# bmc.net
KiCad netlist of a schematic drawn in EAGLE
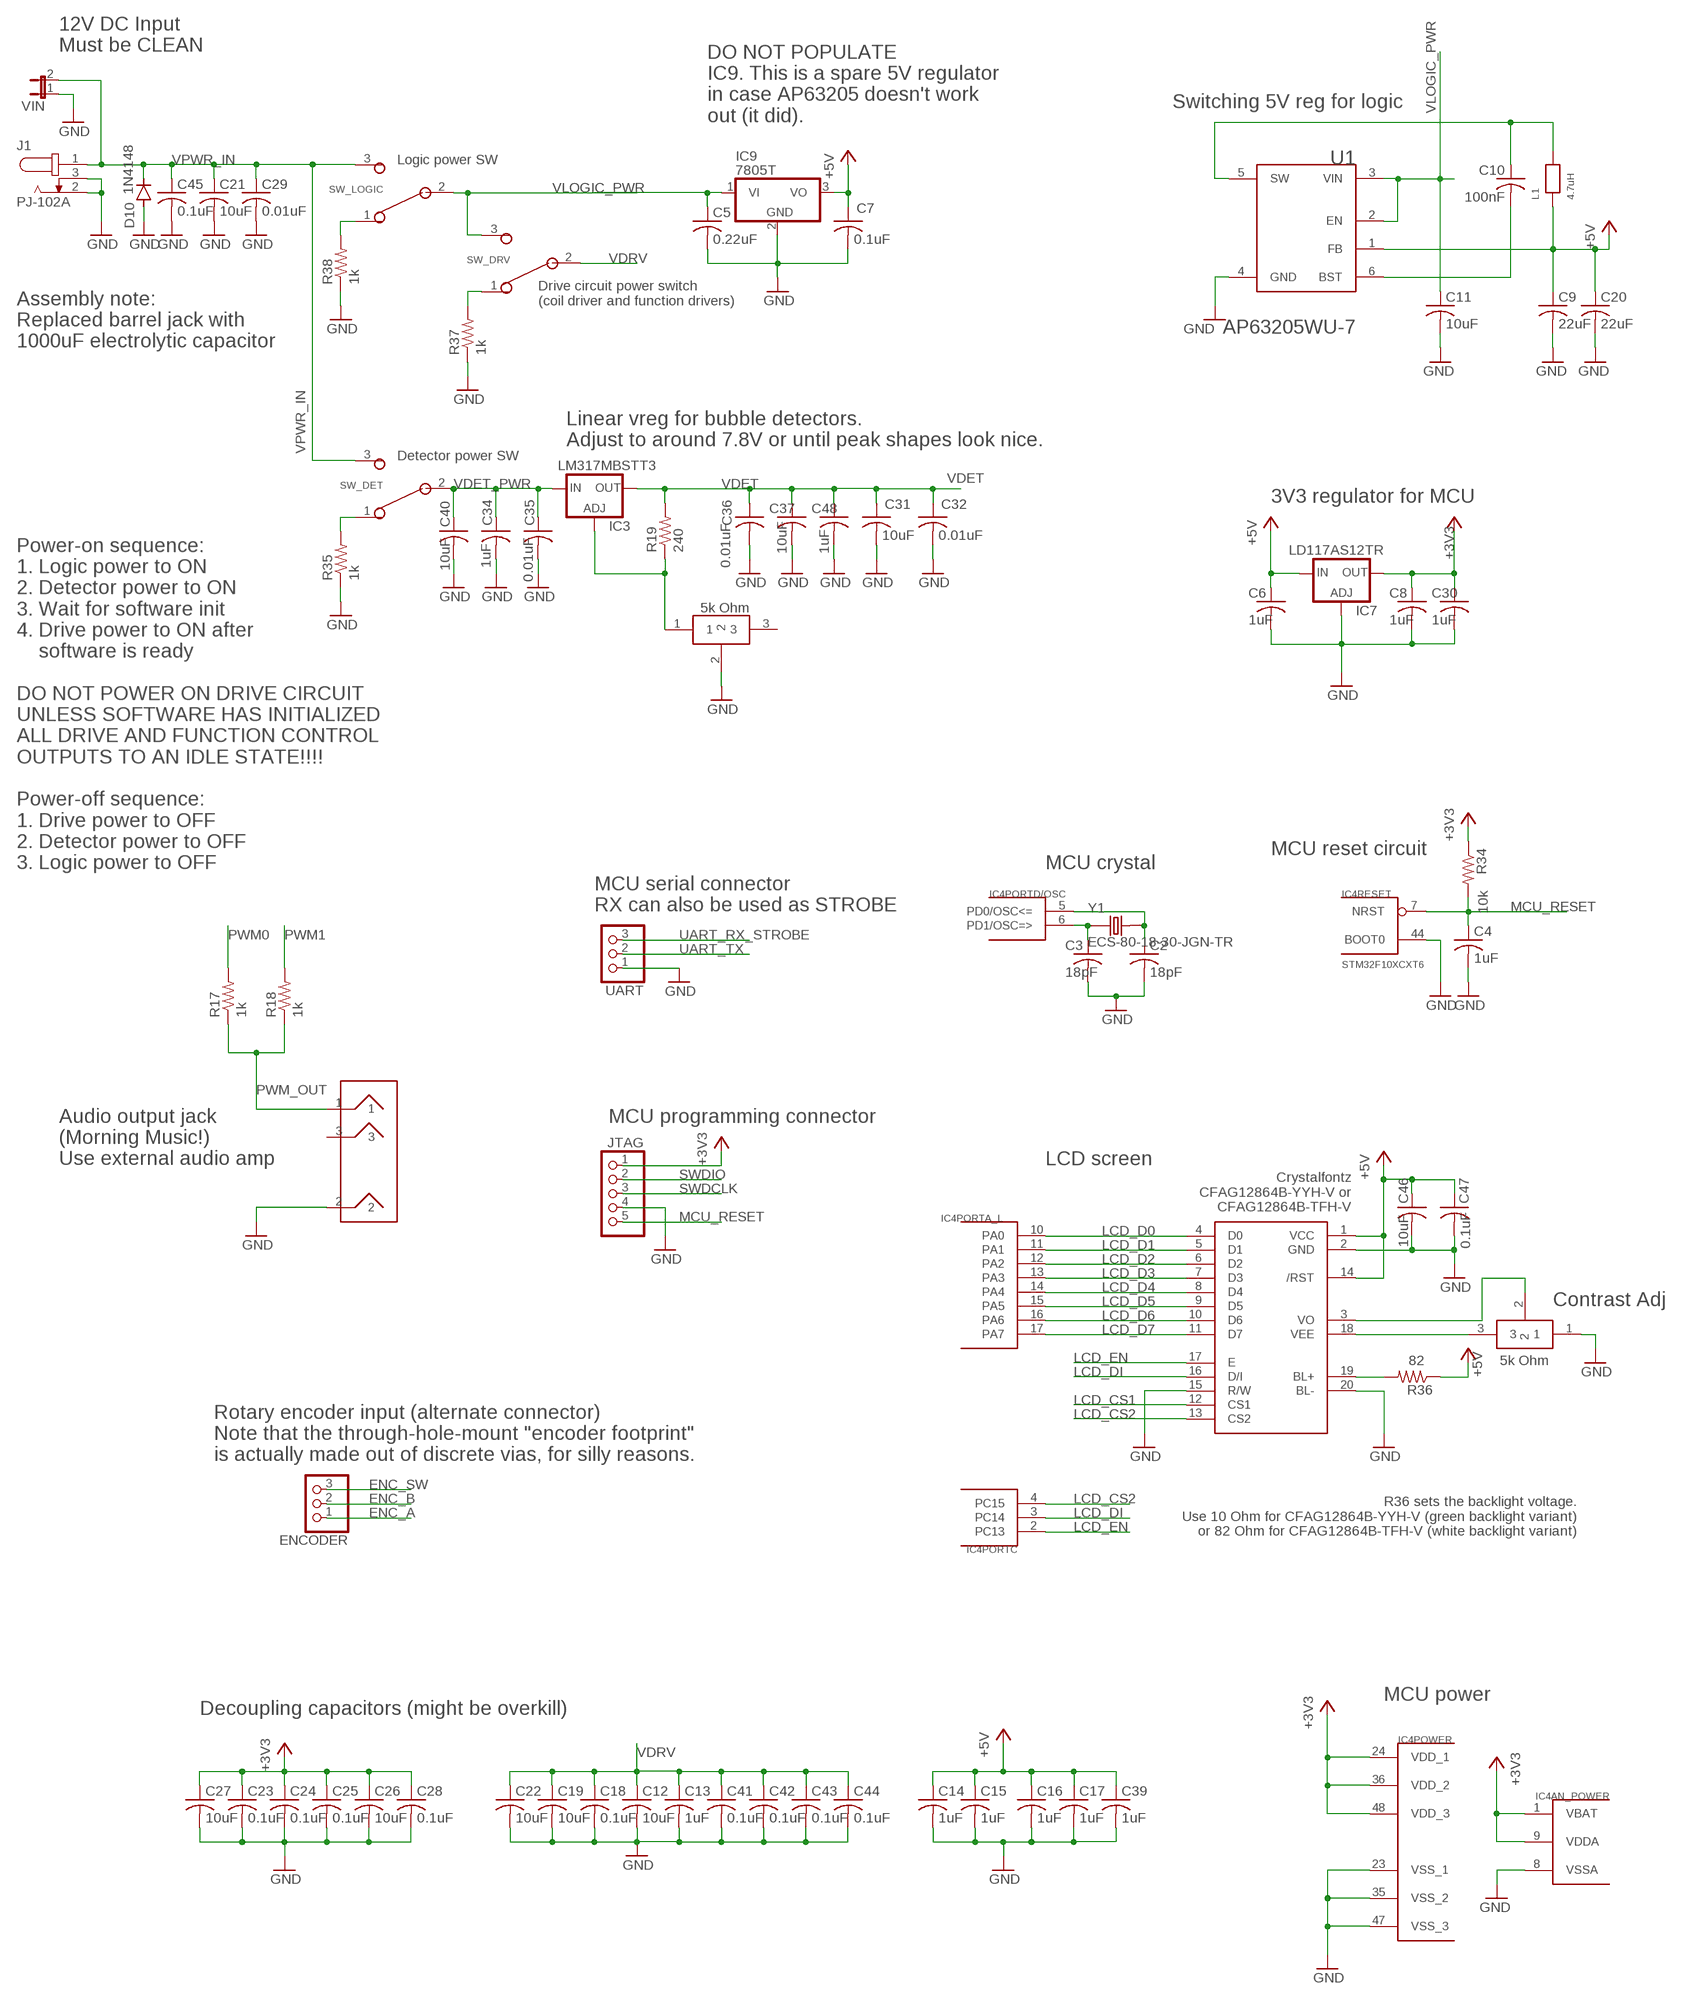
[diagram p0: schematic, sheet 1, part 1 of 2]
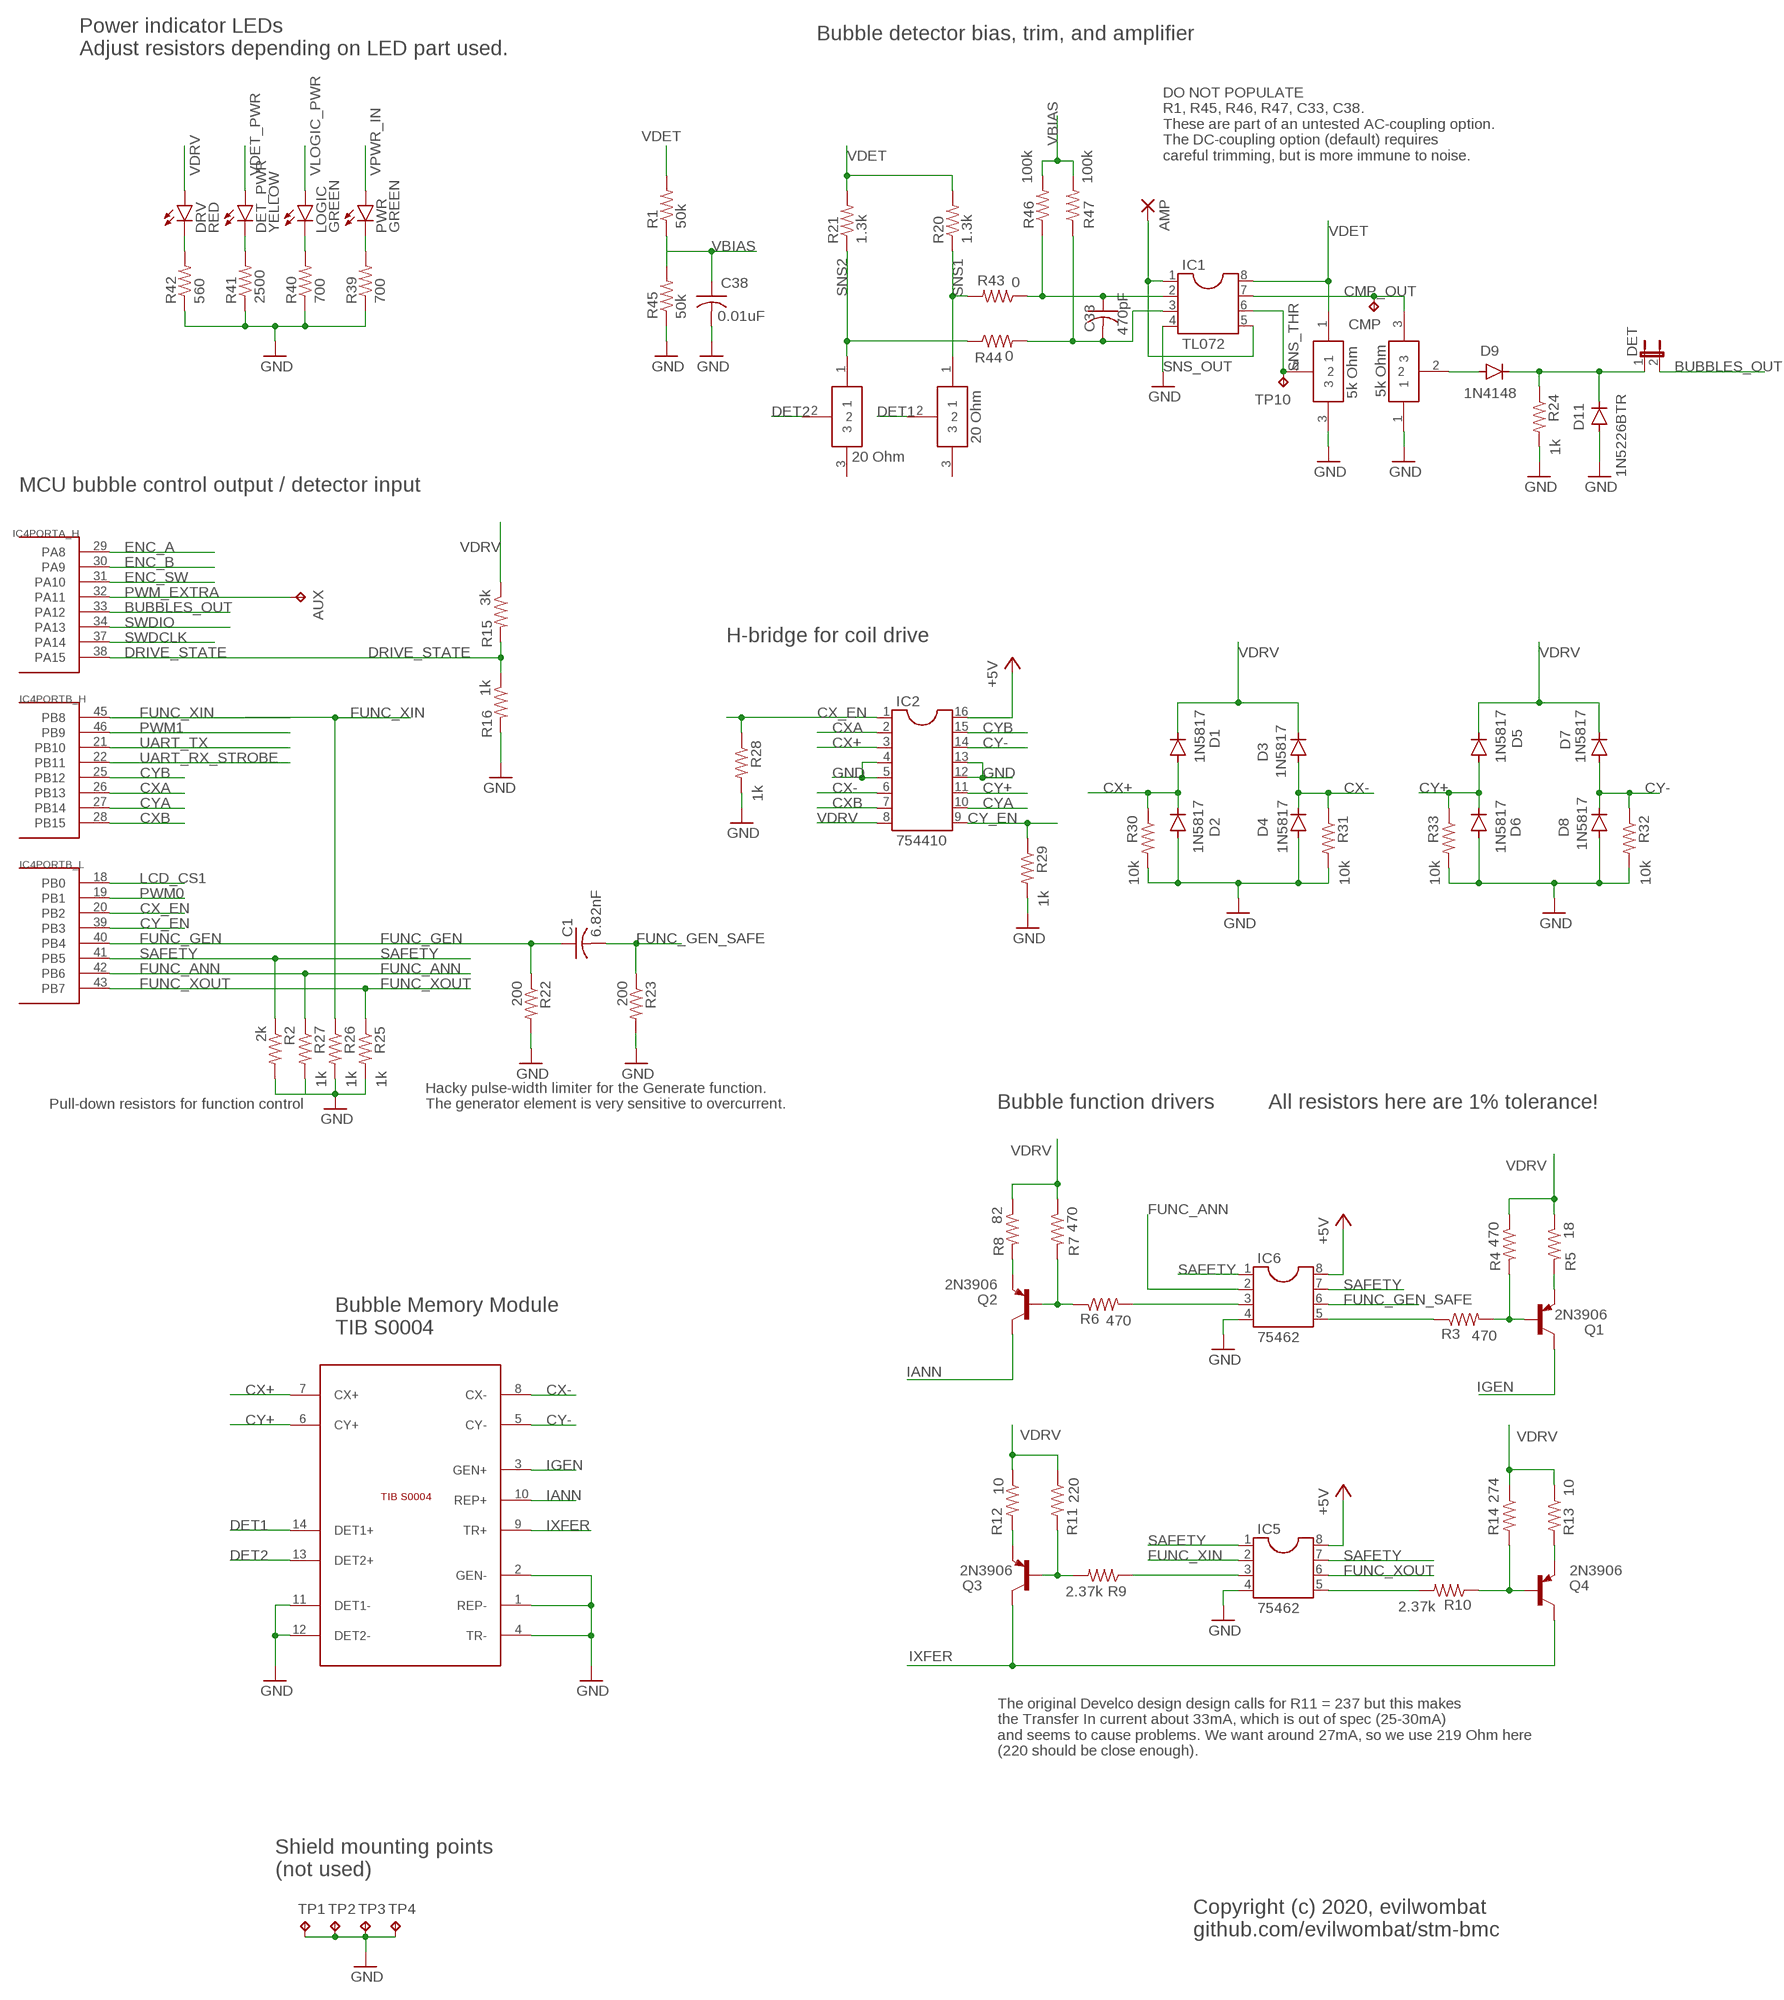
[diagram p1: schematic, sheet 1, part 2 of 2]

(export (version "E")
  (design (tool "Eeschema 10.0.6"))
  (components
    (comp (ref "AMP")
      (value "1,6/0,8")
      (footprint "eagle-import:1,6_0,8")
      (libsource (lib "eagle-import") (part "1,6/0,8"))
    )
    (comp (ref "AUX")
      (value "TPTP07R")
      (footprint "eagle-import:TP07R")
      (libsource (lib "eagle-import") (part "TPTP07R"))
    )
    (comp (ref "C1")
      (value "6.82nF")
      (footprint "eagle-import:CAPC2012X110")
      (libsource (lib "eagle-import") (part "C-USCHIP-0805(2012-METRIC)_"))
    )
    (comp (ref "C2")
      (value "18pF")
      (footprint "eagle-import:CAPC2012X110")
      (libsource (lib "eagle-import") (part "C-USCHIP-0805(2012-METRIC)_"))
    )
    (comp (ref "C3")
      (value "18pF")
      (footprint "eagle-import:CAPC2012X110")
      (libsource (lib "eagle-import") (part "C-USCHIP-0805(2012-METRIC)_"))
    )
    (comp (ref "C4")
      (value "1uF")
      (footprint "eagle-import:CAPC2012X110")
      (libsource (lib "eagle-import") (part "C-USCHIP-0805(2012-METRIC)_"))
    )
    (comp (ref "C5")
      (value "0.22uF")
      (footprint "eagle-import:CAPC2012X110")
      (libsource (lib "eagle-import") (part "C-USCHIP-0805(2012-METRIC)_"))
    )
    (comp (ref "C6")
      (value "1uF")
      (footprint "eagle-import:CAPC2012X110")
      (libsource (lib "eagle-import") (part "C-USCHIP-0805(2012-METRIC)_"))
    )
    (comp (ref "C7")
      (value "0.1uF")
      (footprint "eagle-import:CAPC2012X110")
      (libsource (lib "eagle-import") (part "C-USCHIP-0805(2012-METRIC)_"))
    )
    (comp (ref "C8")
      (value "1uF")
      (footprint "eagle-import:CAPC2012X110")
      (libsource (lib "eagle-import") (part "C-USCHIP-0805(2012-METRIC)_"))
    )
    (comp (ref "C9")
      (value "22uF")
      (footprint "eagle-import:CAPC2012X110")
      (libsource (lib "eagle-import") (part "C-USCHIP-0805(2012-METRIC)_"))
    )
    (comp (ref "C10")
      (value "100nF")
      (footprint "eagle-import:CAPC2012X110")
      (libsource (lib "eagle-import") (part "C-USCHIP-0805(2012-METRIC)_"))
    )
    (comp (ref "C11")
      (value "10uF")
      (footprint "eagle-import:CAPC3216X135")
      (libsource (lib "eagle-import") (part "C-USCHIP-1206(3216-METRIC)_"))
    )
    (comp (ref "C12")
      (value "10uF")
      (footprint "eagle-import:CAPC3216X135")
      (libsource (lib "eagle-import") (part "C-USCHIP-1206(3216-METRIC)_"))
    )
    (comp (ref "C13")
      (value "1uF")
      (footprint "eagle-import:CAPC2012X110")
      (libsource (lib "eagle-import") (part "C-USCHIP-0805(2012-METRIC)_"))
    )
    (comp (ref "C14")
      (value "1uF")
      (footprint "eagle-import:CAPC2012X110")
      (libsource (lib "eagle-import") (part "C-USCHIP-0805(2012-METRIC)_"))
    )
    (comp (ref "C15")
      (value "1uF")
      (footprint "eagle-import:CAPC2012X110")
      (libsource (lib "eagle-import") (part "C-USCHIP-0805(2012-METRIC)_"))
    )
    (comp (ref "C16")
      (value "1uF")
      (footprint "eagle-import:CAPC2012X110")
      (libsource (lib "eagle-import") (part "C-USCHIP-0805(2012-METRIC)_"))
    )
    (comp (ref "C17")
      (value "1uF")
      (footprint "eagle-import:CAPC2012X110")
      (libsource (lib "eagle-import") (part "C-USCHIP-0805(2012-METRIC)_"))
    )
    (comp (ref "C18")
      (value "0.1uF")
      (footprint "eagle-import:CAPC2012X110")
      (libsource (lib "eagle-import") (part "C-USCHIP-0805(2012-METRIC)_"))
    )
    (comp (ref "C19")
      (value "10uF")
      (footprint "eagle-import:CAPC3216X135")
      (libsource (lib "eagle-import") (part "C-USCHIP-1206(3216-METRIC)_"))
    )
    (comp (ref "C20")
      (value "22uF")
      (footprint "eagle-import:CAPC2012X110")
      (libsource (lib "eagle-import") (part "C-USCHIP-0805(2012-METRIC)_"))
    )
    (comp (ref "C21")
      (value "10uF")
      (footprint "eagle-import:CAPC3216X135")
      (libsource (lib "eagle-import") (part "C-USCHIP-1206(3216-METRIC)_"))
    )
    (comp (ref "C22")
      (value "10uF")
      (footprint "eagle-import:CAPC3216X135")
      (libsource (lib "eagle-import") (part "C-USCHIP-1206(3216-METRIC)_"))
    )
    (comp (ref "C23")
      (value "0.1uF")
      (footprint "eagle-import:CAPC1005X60")
      (libsource (lib "eagle-import") (part "C-USCHIP-0402(1005-METRIC)_"))
    )
    (comp (ref "C24")
      (value "0.1uF")
      (footprint "eagle-import:CAPC1005X60")
      (libsource (lib "eagle-import") (part "C-USCHIP-0402(1005-METRIC)_"))
    )
    (comp (ref "C25")
      (value "0.1uF")
      (footprint "eagle-import:CAPC1005X60")
      (libsource (lib "eagle-import") (part "C-USCHIP-0402(1005-METRIC)_"))
    )
    (comp (ref "C26")
      (value "10uF")
      (footprint "eagle-import:CAPC2012X110")
      (libsource (lib "eagle-import") (part "C-USCHIP-0805(2012-METRIC)_"))
    )
    (comp (ref "C27")
      (value "10uF")
      (footprint "eagle-import:CAPC2012X110")
      (libsource (lib "eagle-import") (part "C-USCHIP-0805(2012-METRIC)_"))
    )
    (comp (ref "C28")
      (value "0.1uF")
      (footprint "eagle-import:CAPC1005X60")
      (libsource (lib "eagle-import") (part "C-USCHIP-0402(1005-METRIC)_"))
    )
    (comp (ref "C29")
      (value "0.01uF")
      (footprint "eagle-import:CAPC2012X110")
      (libsource (lib "eagle-import") (part "C-USCHIP-0805(2012-METRIC)_"))
    )
    (comp (ref "C30")
      (value "1uF")
      (footprint "eagle-import:CAPC2012X110")
      (libsource (lib "eagle-import") (part "C-USCHIP-0805(2012-METRIC)_"))
    )
    (comp (ref "C31")
      (value "10uF")
      (footprint "eagle-import:CAPC3216X135")
      (libsource (lib "eagle-import") (part "C-USCHIP-1206(3216-METRIC)_"))
    )
    (comp (ref "C32")
      (value "0.01uF")
      (footprint "eagle-import:CAPC2012X110")
      (libsource (lib "eagle-import") (part "C-USCHIP-0805(2012-METRIC)_"))
    )
    (comp (ref "C33")
      (value "470pF")
      (footprint "eagle-import:CAPC2012X110")
      (libsource (lib "eagle-import") (part "C-USCHIP-0805(2012-METRIC)_"))
    )
    (comp (ref "C34")
      (value "1uF")
      (footprint "eagle-import:CAPC2012X110")
      (libsource (lib "eagle-import") (part "C-USCHIP-0805(2012-METRIC)_"))
    )
    (comp (ref "C35")
      (value "0.01uF")
      (footprint "eagle-import:CAPC2012X110")
      (libsource (lib "eagle-import") (part "C-USCHIP-0805(2012-METRIC)_"))
    )
    (comp (ref "C36")
      (value "0.01uF")
      (footprint "eagle-import:CAPC2012X110")
      (libsource (lib "eagle-import") (part "C-USCHIP-0805(2012-METRIC)_"))
    )
    (comp (ref "C37")
      (value "10uF")
      (footprint "eagle-import:CAPC3216X135")
      (libsource (lib "eagle-import") (part "C-USCHIP-1206(3216-METRIC)_"))
    )
    (comp (ref "C38")
      (value "0.01uF")
      (footprint "eagle-import:CAPC2012X110")
      (libsource (lib "eagle-import") (part "C-USCHIP-0805(2012-METRIC)_"))
    )
    (comp (ref "C39")
      (value "1uF")
      (footprint "eagle-import:CAPC2012X110")
      (libsource (lib "eagle-import") (part "C-USCHIP-0805(2012-METRIC)_"))
    )
    (comp (ref "C40")
      (value "10uF")
      (footprint "eagle-import:CAPC3216X135")
      (libsource (lib "eagle-import") (part "C-USCHIP-1206(3216-METRIC)_"))
    )
    (comp (ref "C41")
      (value "0.1uF")
      (footprint "eagle-import:CAPC2012X110")
      (libsource (lib "eagle-import") (part "C-USCHIP-0805(2012-METRIC)_"))
    )
    (comp (ref "C42")
      (value "0.1uF")
      (footprint "eagle-import:CAPC2012X110")
      (libsource (lib "eagle-import") (part "C-USCHIP-0805(2012-METRIC)_"))
    )
    (comp (ref "C43")
      (value "0.1uF")
      (footprint "eagle-import:CAPC2012X110")
      (libsource (lib "eagle-import") (part "C-USCHIP-0805(2012-METRIC)_"))
    )
    (comp (ref "C44")
      (value "0.1uF")
      (footprint "eagle-import:CAPC2012X110")
      (libsource (lib "eagle-import") (part "C-USCHIP-0805(2012-METRIC)_"))
    )
    (comp (ref "C45")
      (value "0.1uF")
      (footprint "eagle-import:CAPC2012X110")
      (libsource (lib "eagle-import") (part "C-USCHIP-0805(2012-METRIC)_"))
    )
    (comp (ref "C46")
      (value "10uF")
      (footprint "eagle-import:CAPC3216X135")
      (libsource (lib "eagle-import") (part "C-USCHIP-1206(3216-METRIC)_"))
    )
    (comp (ref "C47")
      (value "0.1uF")
      (footprint "eagle-import:CAPC2012X110")
      (libsource (lib "eagle-import") (part "C-USCHIP-0805(2012-METRIC)_"))
    )
    (comp (ref "C48")
      (value "1uF")
      (footprint "eagle-import:CAPC2012X110")
      (libsource (lib "eagle-import") (part "C-USCHIP-0805(2012-METRIC)_"))
    )
    (comp (ref "CMP")
      (value "TPTP07R")
      (footprint "eagle-import:TP07R")
      (libsource (lib "eagle-import") (part "TPTP07R"))
    )
    (comp (ref "D1")
      (value "1N5817")
      (footprint "eagle-import:DO-41")
      (fields
        (field (name "DIGIKEY_PART_NUMBER") "1N4004MSCT-ND")
        (field (name "MANUFACTURER") "Micro Commercial Co")
        (field (name "MPN") "1N4004")
        (field (name "CREATED_BY") "PCBLayout.com")
      )
      (libsource (lib "eagle-import") (part "1N4004"))
    )
    (comp (ref "D2")
      (value "1N5817")
      (footprint "eagle-import:DO-41")
      (fields
        (field (name "DIGIKEY_PART_NUMBER") "1N4004MSCT-ND")
        (field (name "MANUFACTURER") "Micro Commercial Co")
        (field (name "MPN") "1N4004")
        (field (name "CREATED_BY") "PCBLayout.com")
      )
      (libsource (lib "eagle-import") (part "1N4004"))
    )
    (comp (ref "D3")
      (value "1N5817")
      (footprint "eagle-import:DO-41")
      (fields
        (field (name "DIGIKEY_PART_NUMBER") "1N4004MSCT-ND")
        (field (name "MANUFACTURER") "Micro Commercial Co")
        (field (name "MPN") "1N4004")
        (field (name "CREATED_BY") "PCBLayout.com")
      )
      (libsource (lib "eagle-import") (part "1N4004"))
    )
    (comp (ref "D4")
      (value "1N5817")
      (footprint "eagle-import:DO-41")
      (fields
        (field (name "DIGIKEY_PART_NUMBER") "1N4004MSCT-ND")
        (field (name "MANUFACTURER") "Micro Commercial Co")
        (field (name "MPN") "1N4004")
        (field (name "CREATED_BY") "PCBLayout.com")
      )
      (libsource (lib "eagle-import") (part "1N4004"))
    )
    (comp (ref "D5")
      (value "1N5817")
      (footprint "eagle-import:DO-41")
      (fields
        (field (name "DIGIKEY_PART_NUMBER") "1N4004MSCT-ND")
        (field (name "MANUFACTURER") "Micro Commercial Co")
        (field (name "MPN") "1N4004")
        (field (name "CREATED_BY") "PCBLayout.com")
      )
      (libsource (lib "eagle-import") (part "1N4004"))
    )
    (comp (ref "D6")
      (value "1N5817")
      (footprint "eagle-import:DO-41")
      (fields
        (field (name "DIGIKEY_PART_NUMBER") "1N4004MSCT-ND")
        (field (name "MANUFACTURER") "Micro Commercial Co")
        (field (name "MPN") "1N4004")
        (field (name "CREATED_BY") "PCBLayout.com")
      )
      (libsource (lib "eagle-import") (part "1N4004"))
    )
    (comp (ref "D7")
      (value "1N5817")
      (footprint "eagle-import:DO-41")
      (fields
        (field (name "DIGIKEY_PART_NUMBER") "1N4004MSCT-ND")
        (field (name "MANUFACTURER") "Micro Commercial Co")
        (field (name "MPN") "1N4004")
        (field (name "CREATED_BY") "PCBLayout.com")
      )
      (libsource (lib "eagle-import") (part "1N4004"))
    )
    (comp (ref "D8")
      (value "1N5817")
      (footprint "eagle-import:DO-41")
      (fields
        (field (name "DIGIKEY_PART_NUMBER") "1N4004MSCT-ND")
        (field (name "MANUFACTURER") "Micro Commercial Co")
        (field (name "MPN") "1N4004")
        (field (name "CREATED_BY") "PCBLayout.com")
      )
      (libsource (lib "eagle-import") (part "1N4004"))
    )
    (comp (ref "D9")
      (value "1N4148")
      (footprint "eagle-import:DO-41")
      (fields
        (field (name "DIGIKEY_PART_NUMBER") "1N4004MSCT-ND")
        (field (name "MANUFACTURER") "Micro Commercial Co")
        (field (name "MPN") "1N4004")
        (field (name "CREATED_BY") "PCBLayout.com")
      )
      (libsource (lib "eagle-import") (part "1N4004"))
    )
    (comp (ref "D10")
      (value "1N4148")
      (footprint "eagle-import:DO-41")
      (fields
        (field (name "DIGIKEY_PART_NUMBER") "1N4004MSCT-ND")
        (field (name "MANUFACTURER") "Micro Commercial Co")
        (field (name "MPN") "1N4004")
        (field (name "CREATED_BY") "PCBLayout.com")
      )
      (libsource (lib "eagle-import") (part "1N4004"))
    )
    (comp (ref "D11")
      (value "1N5226BTR")
      (footprint "eagle-import:DO-41")
      (fields
        (field (name "DIGIKEY_PART_NUMBER") "1N4004MSCT-ND")
        (field (name "MANUFACTURER") "Micro Commercial Co")
        (field (name "MPN") "1N4004")
        (field (name "CREATED_BY") "PCBLayout.com")
      )
      (libsource (lib "eagle-import") (part "1N4004"))
    )
    (comp (ref "DET")
      (value "JP1E")
      (footprint "eagle-import:JP1")
      (libsource (lib "eagle-import") (part "JP1E"))
    )
    (comp (ref "DET_PWR")
      (value "YELLOW")
      (footprint "eagle-import:CHIPLED_1206")
      (libsource (lib "eagle-import") (part "LEDCHIPLED_1206"))
    )
    (comp (ref "DISP1")
      (value "CFAG12864B")
      (footprint "eagle-import:CFAG16864B")
      (libsource (lib "eagle-import") (part "CFAG12864B"))
    )
    (comp (ref "DRV")
      (value "RED")
      (footprint "eagle-import:CHIPLED_1206")
      (libsource (lib "eagle-import") (part "LEDCHIPLED_1206"))
    )
    (comp (ref "ENCODER")
      (value "PINHD-1X3")
      (footprint "eagle-import:1X03")
      (libsource (lib "eagle-import") (part "PINHD-1X3"))
    )
    (comp (ref "IC1")
      (value "TL072")
      (footprint "eagle-import:DIL08")
      (libsource (lib "eagle-import") (part "DIL8"))
    )
    (comp (ref "IC2")
      (value "754410")
      (footprint "eagle-import:DIL16")
      (libsource (lib "eagle-import") (part "DIL16"))
    )
    (comp (ref "IC3")
      (value "LM317MBSTT3")
      (footprint "eagle-import:SOT223")
      (libsource (lib "eagle-import") (part "LM317?MBSTT3"))
    )
    (comp (ref "IC4")
      (value "STM32F10XCXT6")
      (footprint "eagle-import:TQFP48")
      (libsource (lib "eagle-import") (part "STM32F10XCXT6"))
    )
    (comp (ref "IC5")
      (value "75462")
      (footprint "eagle-import:DIL08")
      (libsource (lib "eagle-import") (part "DIL8"))
    )
    (comp (ref "IC6")
      (value "75462")
      (footprint "eagle-import:DIL08")
      (libsource (lib "eagle-import") (part "DIL8"))
    )
    (comp (ref "IC7")
      (value "LD117AS12TR")
      (footprint "eagle-import:SOT223")
      (libsource (lib "eagle-import") (part "LD117A?S12TR"))
    )
    (comp (ref "IC9")
      (value "7805T")
      (footprint "eagle-import:TO220H")
      (libsource (lib "eagle-import") (part "78T05"))
    )
    (comp (ref "J1")
      (value "PJ-102A")
      (footprint "eagle-import:CUI_PJ-102A")
      (fields (field (name "MANUFACTURER") "CUI INC"))
      (libsource (lib "eagle-import") (part "PJ-102A"))
    )
    (comp (ref "JTAG")
      (value "PINHD-1X5")
      (footprint "eagle-import:1X05")
      (libsource (lib "eagle-import") (part "PINHD-1X5"))
    )
    (comp (ref "L1")
      (value "4.7uH")
      (footprint "eagle-import:WE-PMI_1008")
      (libsource (lib "eagle-import") (part "IND-10081008"))
    )
    (comp (ref "LOGIC")
      (value "GREEN")
      (footprint "eagle-import:CHIPLED_1206")
      (libsource (lib "eagle-import") (part "LEDCHIPLED_1206"))
    )
    (comp (ref "MUSIC_OUT")
      (value "STX-3501-3N")
      (footprint "eagle-import:STX-3501-3N")
      (libsource (lib "eagle-import") (part "STX-3501-3N"))
    )
    (comp (ref "OLVL")
      (value "PV36W")
      (footprint "eagle-import:PV36W")
      (libsource (lib "eagle-import") (part "PV36W"))
    )
    (comp (ref "PWR")
      (value "GREEN")
      (footprint "eagle-import:CHIPLED_1206")
      (libsource (lib "eagle-import") (part "LEDCHIPLED_1206"))
    )
    (comp (ref "Q1")
      (value "2N3906")
      (footprint "eagle-import:TO92")
      (libsource (lib "eagle-import") (part "2N3906"))
    )
    (comp (ref "Q2")
      (value "2N3906")
      (footprint "eagle-import:TO92")
      (libsource (lib "eagle-import") (part "2N3906"))
    )
    (comp (ref "Q3")
      (value "2N3906")
      (footprint "eagle-import:TO92")
      (libsource (lib "eagle-import") (part "2N3906"))
    )
    (comp (ref "Q4")
      (value "2N3906")
      (footprint "eagle-import:TO92")
      (libsource (lib "eagle-import") (part "2N3906"))
    )
    (comp (ref "R1")
      (value "50k")
      (footprint "eagle-import:R0805")
      (libsource (lib "eagle-import") (part "R-US_R0805"))
    )
    (comp (ref "R2")
      (value "2k")
      (footprint "eagle-import:R0805")
      (libsource (lib "eagle-import") (part "R-US_R0805"))
    )
    (comp (ref "R3")
      (value "470")
      (footprint "eagle-import:R0805")
      (libsource (lib "eagle-import") (part "R-US_R0805"))
    )
    (comp (ref "R4")
      (value "470")
      (footprint "eagle-import:R0805")
      (libsource (lib "eagle-import") (part "R-US_R0805"))
    )
    (comp (ref "R5")
      (value "18")
      (footprint "eagle-import:R0805")
      (libsource (lib "eagle-import") (part "R-US_R0805"))
    )
    (comp (ref "R6")
      (value "470")
      (footprint "eagle-import:R0805")
      (libsource (lib "eagle-import") (part "R-US_R0805"))
    )
    (comp (ref "R7")
      (value "470")
      (footprint "eagle-import:R0805")
      (libsource (lib "eagle-import") (part "R-US_R0805"))
    )
    (comp (ref "R8")
      (value "82")
      (footprint "eagle-import:R0805")
      (libsource (lib "eagle-import") (part "R-US_R0805"))
    )
    (comp (ref "R9")
      (value "2.37k")
      (footprint "eagle-import:R0805")
      (libsource (lib "eagle-import") (part "R-US_R0805"))
    )
    (comp (ref "R10")
      (value "2.37k")
      (footprint "eagle-import:R0805")
      (libsource (lib "eagle-import") (part "R-US_R0805"))
    )
    (comp (ref "R11")
      (value "220")
      (footprint "eagle-import:R0805")
      (libsource (lib "eagle-import") (part "R-US_R0805"))
    )
    (comp (ref "R12")
      (value "10")
      (footprint "eagle-import:R0805")
      (libsource (lib "eagle-import") (part "R-US_R0805"))
    )
    (comp (ref "R13")
      (value "10")
      (footprint "eagle-import:R0805")
      (libsource (lib "eagle-import") (part "R-US_R0805"))
    )
    (comp (ref "R14")
      (value "274")
      (footprint "eagle-import:R0805")
      (libsource (lib "eagle-import") (part "R-US_R0805"))
    )
    (comp (ref "R15")
      (value "3k")
      (footprint "eagle-import:R0805")
      (libsource (lib "eagle-import") (part "R-US_R0805"))
    )
    (comp (ref "R16")
      (value "1k")
      (footprint "eagle-import:R0805")
      (libsource (lib "eagle-import") (part "R-US_R0805"))
    )
    (comp (ref "R17")
      (value "1k")
      (footprint "eagle-import:R0805")
      (libsource (lib "eagle-import") (part "R-US_R0805"))
    )
    (comp (ref "R18")
      (value "1k")
      (footprint "eagle-import:R0805")
      (libsource (lib "eagle-import") (part "R-US_R0805"))
    )
    (comp (ref "R19")
      (value "240")
      (footprint "eagle-import:R0805")
      (libsource (lib "eagle-import") (part "R-US_R0805"))
    )
    (comp (ref "R20")
      (value "1.3k")
      (footprint "eagle-import:0204_7")
      (libsource (lib "eagle-import") (part "R-US_0204/7"))
    )
    (comp (ref "R21")
      (value "1.3k")
      (footprint "eagle-import:0204_7")
      (libsource (lib "eagle-import") (part "R-US_0204/7"))
    )
    (comp (ref "R22")
      (value "200")
      (footprint "eagle-import:R0805")
      (libsource (lib "eagle-import") (part "R-US_R0805"))
    )
    (comp (ref "R23")
      (value "200")
      (footprint "eagle-import:R0805")
      (libsource (lib "eagle-import") (part "R-US_R0805"))
    )
    (comp (ref "R24")
      (value "1k")
      (footprint "eagle-import:R0805")
      (libsource (lib "eagle-import") (part "R-US_R0805"))
    )
    (comp (ref "R25")
      (value "1k")
      (footprint "eagle-import:R0805")
      (libsource (lib "eagle-import") (part "R-US_R0805"))
    )
    (comp (ref "R26")
      (value "1k")
      (footprint "eagle-import:R0805")
      (libsource (lib "eagle-import") (part "R-US_R0805"))
    )
    (comp (ref "R27")
      (value "1k")
      (footprint "eagle-import:R0805")
      (libsource (lib "eagle-import") (part "R-US_R0805"))
    )
    (comp (ref "R28")
      (value "1k")
      (footprint "eagle-import:R0805")
      (libsource (lib "eagle-import") (part "R-US_R0805"))
    )
    (comp (ref "R29")
      (value "1k")
      (footprint "eagle-import:R0805")
      (libsource (lib "eagle-import") (part "R-US_R0805"))
    )
    (comp (ref "R30")
      (value "10k")
      (footprint "eagle-import:R0805")
      (libsource (lib "eagle-import") (part "R-US_R0805"))
    )
    (comp (ref "R31")
      (value "10k")
      (footprint "eagle-import:R0805")
      (libsource (lib "eagle-import") (part "R-US_R0805"))
    )
    (comp (ref "R32")
      (value "10k")
      (footprint "eagle-import:R0805")
      (libsource (lib "eagle-import") (part "R-US_R0805"))
    )
    (comp (ref "R33")
      (value "10k")
      (footprint "eagle-import:R0805")
      (libsource (lib "eagle-import") (part "R-US_R0805"))
    )
    (comp (ref "R34")
      (value "10k")
      (footprint "eagle-import:R0805")
      (libsource (lib "eagle-import") (part "R-US_R0805"))
    )
    (comp (ref "R35")
      (value "1k")
      (footprint "eagle-import:R0805")
      (libsource (lib "eagle-import") (part "R-US_R0805"))
    )
    (comp (ref "R36")
      (value "82")
      (footprint "eagle-import:R1206")
      (libsource (lib "eagle-import") (part "R-US_R1206"))
    )
    (comp (ref "R37")
      (value "1k")
      (footprint "eagle-import:R0805")
      (libsource (lib "eagle-import") (part "R-US_R0805"))
    )
    (comp (ref "R38")
      (value "1k")
      (footprint "eagle-import:R0805")
      (libsource (lib "eagle-import") (part "R-US_R0805"))
    )
    (comp (ref "R39")
      (value "700")
      (footprint "eagle-import:R0805")
      (libsource (lib "eagle-import") (part "R-US_R0805"))
    )
    (comp (ref "R40")
      (value "700")
      (footprint "eagle-import:R0805")
      (libsource (lib "eagle-import") (part "R-US_R0805"))
    )
    (comp (ref "R41")
      (value "2500")
      (footprint "eagle-import:R0805")
      (libsource (lib "eagle-import") (part "R-US_R0805"))
    )
    (comp (ref "R42")
      (value "560")
      (footprint "eagle-import:R0805")
      (libsource (lib "eagle-import") (part "R-US_R0805"))
    )
    (comp (ref "R43")
      (value "0")
      (footprint "eagle-import:R0805")
      (libsource (lib "eagle-import") (part "R-US_R0805"))
    )
    (comp (ref "R44")
      (value "0")
      (footprint "eagle-import:R0805")
      (libsource (lib "eagle-import") (part "R-US_R0805"))
    )
    (comp (ref "R45")
      (value "50k")
      (footprint "eagle-import:R0805")
      (libsource (lib "eagle-import") (part "R-US_R0805"))
    )
    (comp (ref "R46")
      (value "100k")
      (footprint "eagle-import:R0805")
      (libsource (lib "eagle-import") (part "R-US_R0805"))
    )
    (comp (ref "R47")
      (value "100k")
      (footprint "eagle-import:R0805")
      (libsource (lib "eagle-import") (part "R-US_R0805"))
    )
    (comp (ref "SW_DET")
      (value "SW_SPDT")
      (footprint "eagle-import:SW_SPDT")
      (libsource (lib "eagle-import") (part "SW_SPDT"))
    )
    (comp (ref "SW_DRV")
      (value "SW_SPDT")
      (footprint "eagle-import:SW_SPDT")
      (libsource (lib "eagle-import") (part "SW_SPDT"))
    )
    (comp (ref "SW_LOGIC")
      (value "SW_SPDT")
      (footprint "eagle-import:SW_SPDT")
      (libsource (lib "eagle-import") (part "SW_SPDT"))
    )
    (comp (ref "THR")
      (value "PV36W")
      (footprint "eagle-import:PV36W")
      (libsource (lib "eagle-import") (part "PV36W"))
    )
    (comp (ref "TP1")
      (value "TPTP20SQ")
      (footprint "eagle-import:TP20SQ")
      (libsource (lib "eagle-import") (part "TPTP20SQ"))
    )
    (comp (ref "TP2")
      (value "TPTP20SQ")
      (footprint "eagle-import:TP20SQ")
      (libsource (lib "eagle-import") (part "TPTP20SQ"))
    )
    (comp (ref "TP3")
      (value "TPTP20SQ")
      (footprint "eagle-import:TP20SQ")
      (libsource (lib "eagle-import") (part "TPTP20SQ"))
    )
    (comp (ref "TP4")
      (value "TPTP20SQ")
      (footprint "eagle-import:TP20SQ")
      (libsource (lib "eagle-import") (part "TPTP20SQ"))
    )
    (comp (ref "TP10")
      (value "TPTP07R")
      (footprint "eagle-import:TP07R")
      (libsource (lib "eagle-import") (part "TPTP07R"))
    )
    (comp (ref "TRIM+")
      (value "PV36W")
      (footprint "eagle-import:PV36W")
      (libsource (lib "eagle-import") (part "PV36W"))
    )
    (comp (ref "TRIM-")
      (value "20 Ohm")
      (footprint "eagle-import:PV36W")
      (libsource (lib "eagle-import") (part "PV36W"))
    )
    (comp (ref "U$1")
      (value "TP3386")
      (footprint "eagle-import:3386-EY5")
      (libsource (lib "eagle-import") (part "TP3386"))
    )
    (comp (ref "U$5")
      (value "TIB_S0004")
      (footprint "eagle-import:MBM")
      (libsource (lib "eagle-import") (part "TIB_S0004"))
    )
    (comp (ref "U1")
      (value "DIODES_INC._AP63205WU-7DIODES_INC._AP63205WU-7_0_3")
      (footprint "eagle-import:DIODES_INC._AP63205WU-7_3")
      (fields
        (field (name "DIGIKEY_PART_NUMBER") "AP63205WU-7DICT-ND")
        (field (name "MF") "Diodes Inc.")
        (field (name "MOUSER_PART_NUMBER") "621-AP63205WU-7")
      )
      (libsource (lib "eagle-import") (part "DIODES_INC._AP63205WU-7DIODES_INC._AP63205WU-7_0_3"))
    )
    (comp (ref "UART")
      (value "PINHD-1X3")
      (footprint "eagle-import:1X03")
      (libsource (lib "eagle-import") (part "PINHD-1X3"))
    )
    (comp (ref "VDET")
      (value "PV36W")
      (footprint "eagle-import:PV36W")
      (libsource (lib "eagle-import") (part "PV36W"))
    )
    (comp (ref "VIN")
      (value "JP1E")
      (footprint "eagle-import:JP1")
      (libsource (lib "eagle-import") (part "JP1E"))
    )
    (comp (ref "Y1")
      (value "ECS-80-18-30-JGN-TR")
      (footprint "eagle-import:XTAL_ECS-80-18-30-JGN-TR")
      (fields (field (name "DIGI-KEY_PART_NUMBER") "XC2103CT-ND") (field (name "MF") "ECS Inc."))
      (libsource (lib "eagle-import") (part "ECS-80-18-30-JGN-TR"))
    )
  )
  (nets
    (net (code "1") (name "+3V3") (class "Default")
      (node (ref "C23") (pin "1") (pinfunction "1_1") (pintype "passive"))
      (node (ref "C24") (pin "1") (pinfunction "1_1") (pintype "passive"))
      (node (ref "C25") (pin "1") (pinfunction "1_1") (pintype "passive"))
      (node (ref "C26") (pin "1") (pinfunction "1_1") (pintype "passive"))
      (node (ref "C27") (pin "1") (pinfunction "1_1") (pintype "passive"))
      (node (ref "C28") (pin "1") (pinfunction "1_1") (pintype "passive"))
      (node (ref "C30") (pin "1") (pinfunction "1_1") (pintype "passive"))
      (node (ref "C8") (pin "1") (pinfunction "1_1") (pintype "passive"))
      (node (ref "IC4") (pin "1") (pinfunction "VBAT_1") (pintype "power_in"))
      (node (ref "IC4") (pin "24") (pinfunction "VDD_1_24") (pintype "power_in"))
      (node (ref "IC4") (pin "36") (pinfunction "VDD_2_36") (pintype "power_in"))
      (node (ref "IC4") (pin "48") (pinfunction "VDD_3_48") (pintype "power_in"))
      (node (ref "IC4") (pin "9") (pinfunction "VDDA_9") (pintype "power_in"))
      (node (ref "IC7") (pin "4") (pinfunction "OUT_4") (pintype "passive"))
      (node (ref "JTAG") (pin "1") (pinfunction "1_1") (pintype "passive"))
      (node (ref "R34") (pin "1") (pinfunction "1_1") (pintype "passive"))
    )
    (net (code "2") (name "+5V") (class "Default")
      (node (ref "C14") (pin "1") (pinfunction "1_1") (pintype "passive"))
      (node (ref "C15") (pin "1") (pinfunction "1_1") (pintype "passive"))
      (node (ref "C16") (pin "1") (pinfunction "1_1") (pintype "passive"))
      (node (ref "C17") (pin "1") (pinfunction "1_1") (pintype "passive"))
      (node (ref "C20") (pin "1") (pinfunction "1_1") (pintype "passive"))
      (node (ref "C39") (pin "1") (pinfunction "1_1") (pintype "passive"))
      (node (ref "C46") (pin "1") (pinfunction "1_1") (pintype "passive"))
      (node (ref "C47") (pin "1") (pinfunction "1_1") (pintype "passive"))
      (node (ref "C6") (pin "1") (pinfunction "1_1") (pintype "passive"))
      (node (ref "C7") (pin "1") (pinfunction "1_1") (pintype "passive"))
      (node (ref "C9") (pin "1") (pinfunction "1_1") (pintype "passive"))
      (node (ref "DISP1") (pin "1") (pinfunction "VCC_1") (pintype "bidirectional"))
      (node (ref "DISP1") (pin "14") (pinfunction "/RST_14") (pintype "bidirectional"))
      (node (ref "IC2") (pin "16") (pinfunction "16_16") (pintype "passive"))
      (node (ref "IC5") (pin "8") (pinfunction "8_8") (pintype "passive"))
      (node (ref "IC6") (pin "8") (pinfunction "8_8") (pintype "passive"))
      (node (ref "IC7") (pin "3") (pinfunction "IN_3") (pintype "input"))
      (node (ref "IC9") (pin "3") (pinfunction "VO_3") (pintype "passive"))
      (node (ref "L1") (pin "1") (pinfunction "P$1_1") (pintype "bidirectional"))
      (node (ref "R36") (pin "1") (pinfunction "1_1") (pintype "passive"))
      (node (ref "U1") (pin "1") (pinfunction "FB_1") (pintype "input"))
    )
    (net (code "3") (name "/BUBBLES_OUT") (class "Default")
      (node (ref "DET") (pin "2") (pinfunction "2_2") (pintype "passive"))
      (node (ref "IC4") (pin "33") (pinfunction "PA12_33") (pintype "bidirectional"))
    )
    (net (code "4") (name "/CMP_OUT") (class "Default")
      (node (ref "CMP") (pin "TP") (pinfunction "TP_TP") (pintype "input"))
      (node (ref "IC1") (pin "7") (pinfunction "7_7") (pintype "passive"))
      (node (ref "OLVL") (pin "3") (pinfunction "3_3") (pintype "bidirectional"))
    )
    (net (code "5") (name "/CX+") (class "Default")
      (node (ref "D1") (pin "A") (pinfunction "A_A") (pintype "passive"))
      (node (ref "D2") (pin "C") (pinfunction "C_C") (pintype "passive"))
      (node (ref "IC2") (pin "3") (pinfunction "3_3") (pintype "passive"))
      (node (ref "R30") (pin "1") (pinfunction "1_1") (pintype "passive"))
      (node (ref "U$5") (pin "7") (pinfunction "CX+_7") (pintype "bidirectional"))
    )
    (net (code "6") (name "/CX-") (class "Default")
      (node (ref "D3") (pin "A") (pinfunction "A_A") (pintype "passive"))
      (node (ref "D4") (pin "C") (pinfunction "C_C") (pintype "passive"))
      (node (ref "IC2") (pin "6") (pinfunction "6_6") (pintype "passive"))
      (node (ref "R31") (pin "1") (pinfunction "1_1") (pintype "passive"))
      (node (ref "U$5") (pin "8") (pinfunction "CX-_8") (pintype "bidirectional"))
    )
    (net (code "7") (name "/CXA") (class "Default")
      (node (ref "IC2") (pin "2") (pinfunction "2_2") (pintype "passive"))
      (node (ref "IC4") (pin "26") (pinfunction "PB13_26") (pintype "bidirectional"))
    )
    (net (code "8") (name "/CXB") (class "Default")
      (node (ref "IC2") (pin "7") (pinfunction "7_7") (pintype "passive"))
      (node (ref "IC4") (pin "28") (pinfunction "PB15_28") (pintype "bidirectional"))
    )
    (net (code "9") (name "/CX_EN") (class "Default")
      (node (ref "IC2") (pin "1") (pinfunction "1_1") (pintype "passive"))
      (node (ref "IC4") (pin "20") (pinfunction "PB2_20") (pintype "bidirectional"))
      (node (ref "R28") (pin "1") (pinfunction "1_1") (pintype "passive"))
    )
    (net (code "10") (name "/CY+") (class "Default")
      (node (ref "D5") (pin "A") (pinfunction "A_A") (pintype "passive"))
      (node (ref "D6") (pin "C") (pinfunction "C_C") (pintype "passive"))
      (node (ref "IC2") (pin "11") (pinfunction "11_11") (pintype "passive"))
      (node (ref "R33") (pin "1") (pinfunction "1_1") (pintype "passive"))
      (node (ref "U$5") (pin "6") (pinfunction "CY+_6") (pintype "bidirectional"))
    )
    (net (code "11") (name "/CY-") (class "Default")
      (node (ref "D7") (pin "A") (pinfunction "A_A") (pintype "passive"))
      (node (ref "D8") (pin "C") (pinfunction "C_C") (pintype "passive"))
      (node (ref "IC2") (pin "14") (pinfunction "14_14") (pintype "passive"))
      (node (ref "R32") (pin "1") (pinfunction "1_1") (pintype "passive"))
      (node (ref "U$5") (pin "5") (pinfunction "CY-_5") (pintype "bidirectional"))
    )
    (net (code "12") (name "/CYA") (class "Default")
      (node (ref "IC2") (pin "10") (pinfunction "10_10") (pintype "passive"))
      (node (ref "IC4") (pin "27") (pinfunction "PB14_27") (pintype "bidirectional"))
    )
    (net (code "13") (name "/CYB") (class "Default")
      (node (ref "IC2") (pin "15") (pinfunction "15_15") (pintype "passive"))
      (node (ref "IC4") (pin "25") (pinfunction "PB12_25") (pintype "bidirectional"))
    )
    (net (code "14") (name "/CY_EN") (class "Default")
      (node (ref "IC2") (pin "9") (pinfunction "9_9") (pintype "passive"))
      (node (ref "IC4") (pin "39") (pinfunction "PB3_39") (pintype "bidirectional"))
      (node (ref "R29") (pin "1") (pinfunction "1_1") (pintype "passive"))
    )
    (net (code "15") (name "/DET1") (class "Default")
      (node (ref "TRIM-") (pin "2") (pinfunction "2_2") (pintype "bidirectional"))
      (node (ref "U$5") (pin "14") (pinfunction "DET1+_14") (pintype "bidirectional"))
    )
    (net (code "16") (name "/DET2") (class "Default")
      (node (ref "TRIM+") (pin "2") (pinfunction "2_2") (pintype "bidirectional"))
      (node (ref "U$5") (pin "13") (pinfunction "DET2+_13") (pintype "bidirectional"))
    )
    (net (code "17") (name "/DRIVE_STATE") (class "Default")
      (node (ref "IC4") (pin "38") (pinfunction "PA15_38") (pintype "bidirectional"))
      (node (ref "R15") (pin "2") (pinfunction "2_2") (pintype "passive"))
      (node (ref "R16") (pin "1") (pinfunction "1_1") (pintype "passive"))
    )
    (net (code "18") (name "/ENC_A") (class "Default")
      (node (ref "ENCODER") (pin "1") (pinfunction "1_1") (pintype "passive"))
      (node (ref "IC4") (pin "29") (pinfunction "PA8_29") (pintype "bidirectional"))
    )
    (net (code "19") (name "/ENC_B") (class "Default")
      (node (ref "ENCODER") (pin "2") (pinfunction "2_2") (pintype "passive"))
      (node (ref "IC4") (pin "30") (pinfunction "PA9_30") (pintype "bidirectional"))
    )
    (net (code "20") (name "/ENC_SW") (class "Default")
      (node (ref "ENCODER") (pin "3") (pinfunction "3_3") (pintype "passive"))
      (node (ref "IC4") (pin "31") (pinfunction "PA10_31") (pintype "bidirectional"))
    )
    (net (code "21") (name "/FUNC_ANN") (class "Default")
      (node (ref "IC4") (pin "42") (pinfunction "PB6_42") (pintype "bidirectional"))
      (node (ref "IC6") (pin "2") (pinfunction "2_2") (pintype "passive"))
      (node (ref "R27") (pin "1") (pinfunction "1_1") (pintype "passive"))
    )
    (net (code "22") (name "/FUNC_GEN") (class "Default")
      (node (ref "C1") (pin "1") (pinfunction "1_1") (pintype "passive"))
      (node (ref "IC4") (pin "40") (pinfunction "PB4_40") (pintype "bidirectional"))
      (node (ref "R22") (pin "1") (pinfunction "1_1") (pintype "passive"))
    )
    (net (code "23") (name "/FUNC_GEN_SAFE") (class "Default")
      (node (ref "C1") (pin "2") (pinfunction "2_2") (pintype "passive"))
      (node (ref "IC6") (pin "6") (pinfunction "6_6") (pintype "passive"))
      (node (ref "R23") (pin "1") (pinfunction "1_1") (pintype "passive"))
    )
    (net (code "24") (name "/FUNC_XIN") (class "Default")
      (node (ref "IC4") (pin "45") (pinfunction "PB8_45") (pintype "bidirectional"))
      (node (ref "IC5") (pin "2") (pinfunction "2_2") (pintype "passive"))
      (node (ref "R26") (pin "1") (pinfunction "1_1") (pintype "passive"))
    )
    (net (code "25") (name "/FUNC_XOUT") (class "Default")
      (node (ref "IC4") (pin "43") (pinfunction "PB7_43") (pintype "bidirectional"))
      (node (ref "IC5") (pin "6") (pinfunction "6_6") (pintype "passive"))
      (node (ref "R25") (pin "1") (pinfunction "1_1") (pintype "passive"))
    )
    (net (code "26") (name "/IANN") (class "Default")
      (node (ref "Q2") (pin "1") (pinfunction "C_1") (pintype "passive"))
      (node (ref "U$5") (pin "10") (pinfunction "REP+_10") (pintype "bidirectional"))
    )
    (net (code "27") (name "/IGEN") (class "Default")
      (node (ref "Q1") (pin "1") (pinfunction "C_1") (pintype "passive"))
      (node (ref "U$5") (pin "3") (pinfunction "GEN+_3") (pintype "bidirectional"))
    )
    (net (code "28") (name "/IXFER") (class "Default")
      (node (ref "Q3") (pin "1") (pinfunction "C_1") (pintype "passive"))
      (node (ref "Q4") (pin "1") (pinfunction "C_1") (pintype "passive"))
      (node (ref "U$5") (pin "9") (pinfunction "TR+_9") (pintype "bidirectional"))
    )
    (net (code "29") (name "/LCD_CS1") (class "Default")
      (node (ref "DISP1") (pin "12") (pinfunction "CS1_12") (pintype "bidirectional"))
      (node (ref "IC4") (pin "18") (pinfunction "PB0_18") (pintype "bidirectional"))
    )
    (net (code "30") (name "/LCD_CS2") (class "Default")
      (node (ref "DISP1") (pin "13") (pinfunction "CS2_13") (pintype "bidirectional"))
      (node (ref "IC4") (pin "4") (pinfunction "PC15_4") (pintype "bidirectional"))
    )
    (net (code "31") (name "/LCD_D0") (class "Default")
      (node (ref "DISP1") (pin "4") (pinfunction "D0_4") (pintype "bidirectional"))
      (node (ref "IC4") (pin "10") (pinfunction "PA0_10") (pintype "bidirectional"))
    )
    (net (code "32") (name "/LCD_D1") (class "Default")
      (node (ref "DISP1") (pin "5") (pinfunction "D1_5") (pintype "bidirectional"))
      (node (ref "IC4") (pin "11") (pinfunction "PA1_11") (pintype "bidirectional"))
    )
    (net (code "33") (name "/LCD_D2") (class "Default")
      (node (ref "DISP1") (pin "6") (pinfunction "D2_6") (pintype "bidirectional"))
      (node (ref "IC4") (pin "12") (pinfunction "PA2_12") (pintype "bidirectional"))
    )
    (net (code "34") (name "/LCD_D3") (class "Default")
      (node (ref "DISP1") (pin "7") (pinfunction "D3_7") (pintype "bidirectional"))
      (node (ref "IC4") (pin "13") (pinfunction "PA3_13") (pintype "bidirectional"))
    )
    (net (code "35") (name "/LCD_D4") (class "Default")
      (node (ref "DISP1") (pin "8") (pinfunction "D4_8") (pintype "bidirectional"))
      (node (ref "IC4") (pin "14") (pinfunction "PA4_14") (pintype "bidirectional"))
    )
    (net (code "36") (name "/LCD_D5") (class "Default")
      (node (ref "DISP1") (pin "9") (pinfunction "D5_9") (pintype "bidirectional"))
      (node (ref "IC4") (pin "15") (pinfunction "PA5_15") (pintype "bidirectional"))
    )
    (net (code "37") (name "/LCD_D6") (class "Default")
      (node (ref "DISP1") (pin "10") (pinfunction "D6_10") (pintype "bidirectional"))
      (node (ref "IC4") (pin "16") (pinfunction "PA6_16") (pintype "bidirectional"))
    )
    (net (code "38") (name "/LCD_D7") (class "Default")
      (node (ref "DISP1") (pin "11") (pinfunction "D7_11") (pintype "bidirectional"))
      (node (ref "IC4") (pin "17") (pinfunction "PA7_17") (pintype "bidirectional"))
    )
    (net (code "39") (name "/LCD_DI") (class "Default")
      (node (ref "DISP1") (pin "16") (pinfunction "D/I_16") (pintype "bidirectional"))
      (node (ref "IC4") (pin "3") (pinfunction "PC14_3") (pintype "bidirectional"))
    )
    (net (code "40") (name "/LCD_EN") (class "Default")
      (node (ref "DISP1") (pin "17") (pinfunction "E_17") (pintype "bidirectional"))
      (node (ref "IC4") (pin "2") (pinfunction "PC13_2") (pintype "bidirectional"))
    )
    (net (code "41") (name "/MCU_RESET") (class "Default")
      (node (ref "C4") (pin "1") (pinfunction "1_1") (pintype "passive"))
      (node (ref "IC4") (pin "7") (pinfunction "NRST_7") (pintype "input"))
      (node (ref "JTAG") (pin "5") (pinfunction "5_5") (pintype "passive"))
      (node (ref "R34") (pin "2") (pinfunction "2_2") (pintype "passive"))
    )
    (net (code "42") (name "/PWM0") (class "Default")
      (node (ref "IC4") (pin "19") (pinfunction "PB1_19") (pintype "bidirectional"))
      (node (ref "R17") (pin "2") (pinfunction "2_2") (pintype "passive"))
    )
    (net (code "43") (name "/PWM1") (class "Default")
      (node (ref "IC4") (pin "46") (pinfunction "PB9_46") (pintype "bidirectional"))
      (node (ref "R18") (pin "2") (pinfunction "2_2") (pintype "passive"))
    )
    (net (code "44") (name "/PWM_EXTRA") (class "Default")
      (node (ref "AUX") (pin "TP") (pinfunction "TP_TP") (pintype "input"))
      (node (ref "IC4") (pin "32") (pinfunction "PA11_32") (pintype "bidirectional"))
    )
    (net (code "45") (name "/PWM_OUT") (class "Default")
      (node (ref "MUSIC_OUT") (pin "1") (pinfunction "1_1") (pintype "bidirectional"))
      (node (ref "R17") (pin "1") (pinfunction "1_1") (pintype "passive"))
      (node (ref "R18") (pin "1") (pinfunction "1_1") (pintype "passive"))
    )
    (net (code "46") (name "/SAFETY") (class "Default")
      (node (ref "IC4") (pin "41") (pinfunction "PB5_41") (pintype "bidirectional"))
      (node (ref "IC5") (pin "1") (pinfunction "1_1") (pintype "passive"))
      (node (ref "IC5") (pin "7") (pinfunction "7_7") (pintype "passive"))
      (node (ref "IC6") (pin "1") (pinfunction "1_1") (pintype "passive"))
      (node (ref "IC6") (pin "7") (pinfunction "7_7") (pintype "passive"))
      (node (ref "R2") (pin "1") (pinfunction "1_1") (pintype "passive"))
    )
    (net (code "47") (name "/SNS1") (class "Default")
      (node (ref "R20") (pin "1") (pinfunction "1_1") (pintype "passive"))
      (node (ref "R43") (pin "2") (pinfunction "2_2") (pintype "passive"))
      (node (ref "TRIM-") (pin "1") (pinfunction "1_1") (pintype "bidirectional"))
    )
    (net (code "48") (name "/SNS2") (class "Default")
      (node (ref "R21") (pin "1") (pinfunction "1_1") (pintype "passive"))
      (node (ref "R44") (pin "1") (pinfunction "1_1") (pintype "passive"))
      (node (ref "TRIM+") (pin "1") (pinfunction "1_1") (pintype "bidirectional"))
    )
    (net (code "49") (name "/SNS_OUT") (class "Default")
      (node (ref "AMP") (pin "1") (pinfunction "P_1") (pintype "passive"))
      (node (ref "IC1") (pin "1") (pinfunction "1_1") (pintype "passive"))
      (node (ref "IC1") (pin "5") (pinfunction "5_5") (pintype "passive"))
    )
    (net (code "50") (name "/SNS_THR") (class "Default")
      (node (ref "IC1") (pin "6") (pinfunction "6_6") (pintype "passive"))
      (node (ref "THR") (pin "2") (pinfunction "2_2") (pintype "bidirectional"))
      (node (ref "TP10") (pin "TP") (pinfunction "TP_TP") (pintype "input"))
    )
    (net (code "51") (name "/SWDCLK") (class "Default")
      (node (ref "IC4") (pin "37") (pinfunction "PA14_37") (pintype "bidirectional"))
      (node (ref "JTAG") (pin "3") (pinfunction "3_3") (pintype "passive"))
    )
    (net (code "52") (name "/SWDIO") (class "Default")
      (node (ref "IC4") (pin "34") (pinfunction "PA13_34") (pintype "bidirectional"))
      (node (ref "JTAG") (pin "2") (pinfunction "2_2") (pintype "passive"))
    )
    (net (code "53") (name "/UART_RX_STROBE") (class "Default")
      (node (ref "IC4") (pin "22") (pinfunction "PB11_22") (pintype "bidirectional"))
      (node (ref "UART") (pin "3") (pinfunction "3_3") (pintype "passive"))
    )
    (net (code "54") (name "/UART_TX") (class "Default")
      (node (ref "IC4") (pin "21") (pinfunction "PB10_21") (pintype "bidirectional"))
      (node (ref "UART") (pin "2") (pinfunction "2_2") (pintype "passive"))
    )
    (net (code "55") (name "/VBIAS") (class "Default")
      (node (ref "C38") (pin "1") (pinfunction "1_1") (pintype "passive"))
      (node (ref "R1") (pin "1") (pinfunction "1_1") (pintype "passive"))
      (node (ref "R45") (pin "2") (pinfunction "2_2") (pintype "passive"))
      (node (ref "R46") (pin "2") (pinfunction "2_2") (pintype "passive"))
      (node (ref "R47") (pin "2") (pinfunction "2_2") (pintype "passive"))
    )
    (net (code "56") (name "/VDET") (class "Default")
      (node (ref "C31") (pin "1") (pinfunction "1_1") (pintype "passive"))
      (node (ref "C32") (pin "1") (pinfunction "1_1") (pintype "passive"))
      (node (ref "C36") (pin "1") (pinfunction "1_1") (pintype "passive"))
      (node (ref "C37") (pin "1") (pinfunction "1_1") (pintype "passive"))
      (node (ref "C48") (pin "1") (pinfunction "1_1") (pintype "passive"))
      (node (ref "IC1") (pin "8") (pinfunction "8_8") (pintype "passive"))
      (node (ref "IC3") (pin "2") (pinfunction "OUT_2") (pintype "passive"))
      (node (ref "IC3") (pin "4") (pinfunction "OUT_4") (pintype "passive"))
      (node (ref "R1") (pin "2") (pinfunction "2_2") (pintype "passive"))
      (node (ref "R19") (pin "2") (pinfunction "2_2") (pintype "passive"))
      (node (ref "R20") (pin "2") (pinfunction "2_2") (pintype "passive"))
      (node (ref "R21") (pin "2") (pinfunction "2_2") (pintype "passive"))
      (node (ref "THR") (pin "1") (pinfunction "1_1") (pintype "bidirectional"))
    )
    (net (code "57") (name "/VDET_PWR") (class "Default")
      (node (ref "C34") (pin "1") (pinfunction "1_1") (pintype "passive"))
      (node (ref "C35") (pin "1") (pinfunction "1_1") (pintype "passive"))
      (node (ref "C40") (pin "1") (pinfunction "1_1") (pintype "passive"))
      (node (ref "DET_PWR") (pin "A") (pinfunction "A_A") (pintype "passive"))
      (node (ref "IC3") (pin "3") (pinfunction "IN_3") (pintype "input"))
      (node (ref "SW_DET") (pin "2") (pinfunction "COM_2") (pintype "bidirectional"))
    )
    (net (code "58") (name "/VDRV") (class "Default")
      (node (ref "C12") (pin "1") (pinfunction "1_1") (pintype "passive"))
      (node (ref "C13") (pin "1") (pinfunction "1_1") (pintype "passive"))
      (node (ref "C18") (pin "1") (pinfunction "1_1") (pintype "passive"))
      (node (ref "C19") (pin "1") (pinfunction "1_1") (pintype "passive"))
      (node (ref "C22") (pin "1") (pinfunction "1_1") (pintype "passive"))
      (node (ref "C41") (pin "1") (pinfunction "1_1") (pintype "passive"))
      (node (ref "C42") (pin "1") (pinfunction "1_1") (pintype "passive"))
      (node (ref "C43") (pin "1") (pinfunction "1_1") (pintype "passive"))
      (node (ref "C44") (pin "1") (pinfunction "1_1") (pintype "passive"))
      (node (ref "D1") (pin "C") (pinfunction "C_C") (pintype "passive"))
      (node (ref "D3") (pin "C") (pinfunction "C_C") (pintype "passive"))
      (node (ref "D5") (pin "C") (pinfunction "C_C") (pintype "passive"))
      (node (ref "D7") (pin "C") (pinfunction "C_C") (pintype "passive"))
      (node (ref "DRV") (pin "A") (pinfunction "A_A") (pintype "passive"))
      (node (ref "IC2") (pin "8") (pinfunction "8_8") (pintype "passive"))
      (node (ref "R11") (pin "1") (pinfunction "1_1") (pintype "passive"))
      (node (ref "R12") (pin "1") (pinfunction "1_1") (pintype "passive"))
      (node (ref "R13") (pin "1") (pinfunction "1_1") (pintype "passive"))
      (node (ref "R14") (pin "1") (pinfunction "1_1") (pintype "passive"))
      (node (ref "R15") (pin "1") (pinfunction "1_1") (pintype "passive"))
      (node (ref "R4") (pin "1") (pinfunction "1_1") (pintype "passive"))
      (node (ref "R5") (pin "1") (pinfunction "1_1") (pintype "passive"))
      (node (ref "R7") (pin "1") (pinfunction "1_1") (pintype "passive"))
      (node (ref "R8") (pin "1") (pinfunction "1_1") (pintype "passive"))
      (node (ref "SW_DRV") (pin "2") (pinfunction "COM_2") (pintype "bidirectional"))
    )
    (net (code "59") (name "/VLOGIC_PWR") (class "Default")
      (node (ref "C11") (pin "1") (pinfunction "1_1") (pintype "passive"))
      (node (ref "C5") (pin "1") (pinfunction "1_1") (pintype "passive"))
      (node (ref "IC9") (pin "1") (pinfunction "VI_1") (pintype "input"))
      (node (ref "LOGIC") (pin "A") (pinfunction "A_A") (pintype "passive"))
      (node (ref "SW_DRV") (pin "3") (pinfunction "NO_3") (pintype "bidirectional"))
      (node (ref "SW_LOGIC") (pin "2") (pinfunction "COM_2") (pintype "bidirectional"))
      (node (ref "U1") (pin "2") (pinfunction "EN_2") (pintype "input"))
      (node (ref "U1") (pin "3") (pinfunction "VIN_3") (pintype "power_in"))
    )
    (net (code "60") (name "/VPWR_IN") (class "Default")
      (node (ref "C21") (pin "1") (pinfunction "1_1") (pintype "passive"))
      (node (ref "C29") (pin "1") (pinfunction "1_1") (pintype "passive"))
      (node (ref "C45") (pin "1") (pinfunction "1_1") (pintype "passive"))
      (node (ref "D10") (pin "C") (pinfunction "C_C") (pintype "passive"))
      (node (ref "J1") (pin "1") (pinfunction "1_1") (pintype "passive"))
      (node (ref "PWR") (pin "A") (pinfunction "A_A") (pintype "passive"))
      (node (ref "SW_DET") (pin "3") (pinfunction "NO_3") (pintype "bidirectional"))
      (node (ref "SW_LOGIC") (pin "3") (pinfunction "NO_3") (pintype "bidirectional"))
      (node (ref "VIN") (pin "2") (pinfunction "2_2") (pintype "passive"))
    )
    (net (code "61") (name "GND") (class "Default")
      (node (ref "C11") (pin "2") (pinfunction "2_2") (pintype "passive"))
      (node (ref "C12") (pin "2") (pinfunction "2_2") (pintype "passive"))
      (node (ref "C13") (pin "2") (pinfunction "2_2") (pintype "passive"))
      (node (ref "C14") (pin "2") (pinfunction "2_2") (pintype "passive"))
      (node (ref "C15") (pin "2") (pinfunction "2_2") (pintype "passive"))
      (node (ref "C16") (pin "2") (pinfunction "2_2") (pintype "passive"))
      (node (ref "C17") (pin "2") (pinfunction "2_2") (pintype "passive"))
      (node (ref "C18") (pin "2") (pinfunction "2_2") (pintype "passive"))
      (node (ref "C19") (pin "2") (pinfunction "2_2") (pintype "passive"))
      (node (ref "C2") (pin "2") (pinfunction "2_2") (pintype "passive"))
      (node (ref "C20") (pin "2") (pinfunction "2_2") (pintype "passive"))
      (node (ref "C21") (pin "2") (pinfunction "2_2") (pintype "passive"))
      (node (ref "C22") (pin "2") (pinfunction "2_2") (pintype "passive"))
      (node (ref "C23") (pin "2") (pinfunction "2_2") (pintype "passive"))
      (node (ref "C24") (pin "2") (pinfunction "2_2") (pintype "passive"))
      (node (ref "C25") (pin "2") (pinfunction "2_2") (pintype "passive"))
      (node (ref "C26") (pin "2") (pinfunction "2_2") (pintype "passive"))
      (node (ref "C27") (pin "2") (pinfunction "2_2") (pintype "passive"))
      (node (ref "C28") (pin "2") (pinfunction "2_2") (pintype "passive"))
      (node (ref "C29") (pin "2") (pinfunction "2_2") (pintype "passive"))
      (node (ref "C3") (pin "2") (pinfunction "2_2") (pintype "passive"))
      (node (ref "C30") (pin "2") (pinfunction "2_2") (pintype "passive"))
      (node (ref "C31") (pin "2") (pinfunction "2_2") (pintype "passive"))
      (node (ref "C32") (pin "2") (pinfunction "2_2") (pintype "passive"))
      (node (ref "C34") (pin "2") (pinfunction "2_2") (pintype "passive"))
      (node (ref "C35") (pin "2") (pinfunction "2_2") (pintype "passive"))
      (node (ref "C36") (pin "2") (pinfunction "2_2") (pintype "passive"))
      (node (ref "C37") (pin "2") (pinfunction "2_2") (pintype "passive"))
      (node (ref "C38") (pin "2") (pinfunction "2_2") (pintype "passive"))
      (node (ref "C39") (pin "2") (pinfunction "2_2") (pintype "passive"))
      (node (ref "C4") (pin "2") (pinfunction "2_2") (pintype "passive"))
      (node (ref "C40") (pin "2") (pinfunction "2_2") (pintype "passive"))
      (node (ref "C41") (pin "2") (pinfunction "2_2") (pintype "passive"))
      (node (ref "C42") (pin "2") (pinfunction "2_2") (pintype "passive"))
      (node (ref "C43") (pin "2") (pinfunction "2_2") (pintype "passive"))
      (node (ref "C44") (pin "2") (pinfunction "2_2") (pintype "passive"))
      (node (ref "C45") (pin "2") (pinfunction "2_2") (pintype "passive"))
      (node (ref "C46") (pin "2") (pinfunction "2_2") (pintype "passive"))
      (node (ref "C47") (pin "2") (pinfunction "2_2") (pintype "passive"))
      (node (ref "C48") (pin "2") (pinfunction "2_2") (pintype "passive"))
      (node (ref "C5") (pin "2") (pinfunction "2_2") (pintype "passive"))
      (node (ref "C6") (pin "2") (pinfunction "2_2") (pintype "passive"))
      (node (ref "C7") (pin "2") (pinfunction "2_2") (pintype "passive"))
      (node (ref "C8") (pin "2") (pinfunction "2_2") (pintype "passive"))
      (node (ref "C9") (pin "2") (pinfunction "2_2") (pintype "passive"))
      (node (ref "D10") (pin "A") (pinfunction "A_A") (pintype "passive"))
      (node (ref "D11") (pin "A") (pinfunction "A_A") (pintype "passive"))
      (node (ref "D2") (pin "A") (pinfunction "A_A") (pintype "passive"))
      (node (ref "D4") (pin "A") (pinfunction "A_A") (pintype "passive"))
      (node (ref "D6") (pin "A") (pinfunction "A_A") (pintype "passive"))
      (node (ref "D8") (pin "A") (pinfunction "A_A") (pintype "passive"))
      (node (ref "DISP1") (pin "15") (pinfunction "R/W_15") (pintype "bidirectional"))
      (node (ref "DISP1") (pin "2") (pinfunction "GND_2") (pintype "bidirectional"))
      (node (ref "DISP1") (pin "20") (pinfunction "BL-_20") (pintype "bidirectional"))
      (node (ref "IC1") (pin "4") (pinfunction "4_4") (pintype "passive"))
      (node (ref "IC2") (pin "12") (pinfunction "12_12") (pintype "passive"))
      (node (ref "IC2") (pin "13") (pinfunction "13_13") (pintype "passive"))
      (node (ref "IC2") (pin "4") (pinfunction "4_4") (pintype "passive"))
      (node (ref "IC2") (pin "5") (pinfunction "5_5") (pintype "passive"))
      (node (ref "IC4") (pin "23") (pinfunction "VSS_1_23") (pintype "power_in"))
      (node (ref "IC4") (pin "35") (pinfunction "VSS_2_35") (pintype "power_in"))
      (node (ref "IC4") (pin "44") (pinfunction "BOOT0_44") (pintype "input"))
      (node (ref "IC4") (pin "47") (pinfunction "VSS_3_47") (pintype "power_in"))
      (node (ref "IC4") (pin "8") (pinfunction "VSSA_8") (pintype "power_in"))
      (node (ref "IC5") (pin "4") (pinfunction "4_4") (pintype "passive"))
      (node (ref "IC6") (pin "4") (pinfunction "4_4") (pintype "passive"))
      (node (ref "IC7") (pin "1") (pinfunction "ADJ_1") (pintype "input"))
      (node (ref "IC9") (pin "2") (pinfunction "GND_2") (pintype "passive"))
      (node (ref "J1") (pin "2") (pinfunction "2_2") (pintype "passive"))
      (node (ref "J1") (pin "3") (pinfunction "3_3") (pintype "passive"))
      (node (ref "JTAG") (pin "4") (pinfunction "4_4") (pintype "passive"))
      (node (ref "MUSIC_OUT") (pin "2") (pinfunction "2_2") (pintype "bidirectional"))
      (node (ref "OLVL") (pin "1") (pinfunction "1_1") (pintype "bidirectional"))
      (node (ref "R16") (pin "2") (pinfunction "2_2") (pintype "passive"))
      (node (ref "R2") (pin "2") (pinfunction "2_2") (pintype "passive"))
      (node (ref "R22") (pin "2") (pinfunction "2_2") (pintype "passive"))
      (node (ref "R23") (pin "2") (pinfunction "2_2") (pintype "passive"))
      (node (ref "R24") (pin "2") (pinfunction "2_2") (pintype "passive"))
      (node (ref "R25") (pin "2") (pinfunction "2_2") (pintype "passive"))
      (node (ref "R26") (pin "2") (pinfunction "2_2") (pintype "passive"))
      (node (ref "R27") (pin "2") (pinfunction "2_2") (pintype "passive"))
      (node (ref "R28") (pin "2") (pinfunction "2_2") (pintype "passive"))
      (node (ref "R29") (pin "2") (pinfunction "2_2") (pintype "passive"))
      (node (ref "R30") (pin "2") (pinfunction "2_2") (pintype "passive"))
      (node (ref "R31") (pin "2") (pinfunction "2_2") (pintype "passive"))
      (node (ref "R32") (pin "2") (pinfunction "2_2") (pintype "passive"))
      (node (ref "R33") (pin "2") (pinfunction "2_2") (pintype "passive"))
      (node (ref "R35") (pin "1") (pinfunction "1_1") (pintype "passive"))
      (node (ref "R37") (pin "1") (pinfunction "1_1") (pintype "passive"))
      (node (ref "R38") (pin "1") (pinfunction "1_1") (pintype "passive"))
      (node (ref "R39") (pin "1") (pinfunction "1_1") (pintype "passive"))
      (node (ref "R40") (pin "1") (pinfunction "1_1") (pintype "passive"))
      (node (ref "R41") (pin "1") (pinfunction "1_1") (pintype "passive"))
      (node (ref "R42") (pin "1") (pinfunction "1_1") (pintype "passive"))
      (node (ref "R45") (pin "1") (pinfunction "1_1") (pintype "passive"))
      (node (ref "THR") (pin "3") (pinfunction "3_3") (pintype "bidirectional"))
      (node (ref "TP1") (pin "TP") (pinfunction "TP_TP") (pintype "input"))
      (node (ref "TP2") (pin "TP") (pinfunction "TP_TP") (pintype "input"))
      (node (ref "TP3") (pin "TP") (pinfunction "TP_TP") (pintype "input"))
      (node (ref "TP4") (pin "TP") (pinfunction "TP_TP") (pintype "input"))
      (node (ref "U$1") (pin "1") (pinfunction "1_1") (pintype "bidirectional"))
      (node (ref "U$5") (pin "1") (pinfunction "REP-_1") (pintype "bidirectional"))
      (node (ref "U$5") (pin "11") (pinfunction "DET1-_11") (pintype "bidirectional"))
      (node (ref "U$5") (pin "12") (pinfunction "DET2-_12") (pintype "bidirectional"))
      (node (ref "U$5") (pin "2") (pinfunction "GEN-_2") (pintype "bidirectional"))
      (node (ref "U$5") (pin "4") (pinfunction "TR-_4") (pintype "bidirectional"))
      (node (ref "U1") (pin "4") (pinfunction "GND_4") (pintype "power_in"))
      (node (ref "UART") (pin "1") (pinfunction "1_1") (pintype "passive"))
      (node (ref "VDET") (pin "2") (pinfunction "2_2") (pintype "bidirectional"))
      (node (ref "VIN") (pin "1") (pinfunction "1_1") (pintype "passive"))
    )
    (net (code "62") (name "Net-(C33-Pad1)") (class "Default")
      (node (ref "C33") (pin "1") (pinfunction "1_1") (pintype "passive"))
      (node (ref "IC1") (pin "2") (pinfunction "2_2") (pintype "passive"))
      (node (ref "R43") (pin "1") (pinfunction "1_1") (pintype "passive"))
      (node (ref "R46") (pin "1") (pinfunction "1_1") (pintype "passive"))
    )
    (net (code "63") (name "Net-(C33-Pad2)") (class "Default")
      (node (ref "C33") (pin "2") (pinfunction "2_2") (pintype "passive"))
      (node (ref "IC1") (pin "3") (pinfunction "3_3") (pintype "passive"))
      (node (ref "R44") (pin "2") (pinfunction "2_2") (pintype "passive"))
      (node (ref "R47") (pin "1") (pinfunction "1_1") (pintype "passive"))
    )
    (net (code "64") (name "Net-(D9-PadA)") (class "Default")
      (node (ref "D9") (pin "A") (pinfunction "A_A") (pintype "passive"))
      (node (ref "OLVL") (pin "2") (pinfunction "2_2") (pintype "bidirectional"))
    )
    (net (code "65") (name "Net-(D11-PadC)") (class "Default")
      (node (ref "D11") (pin "C") (pinfunction "C_C") (pintype "passive"))
      (node (ref "D9") (pin "C") (pinfunction "C_C") (pintype "passive"))
      (node (ref "DET") (pin "1") (pinfunction "1_1") (pintype "passive"))
      (node (ref "R24") (pin "1") (pinfunction "1_1") (pintype "passive"))
    )
    (net (code "66") (name "Net-(DET_PWR-PadC)") (class "Default")
      (node (ref "DET_PWR") (pin "C") (pinfunction "C_C") (pintype "passive"))
      (node (ref "R41") (pin "2") (pinfunction "2_2") (pintype "passive"))
    )
    (net (code "67") (name "Net-(DISP1-BL+)") (class "Default")
      (node (ref "DISP1") (pin "19") (pinfunction "BL+_19") (pintype "bidirectional"))
      (node (ref "R36") (pin "2") (pinfunction "2_2") (pintype "passive"))
    )
    (net (code "68") (name "Net-(DISP1-VEE)") (class "Default")
      (node (ref "DISP1") (pin "18") (pinfunction "VEE_18") (pintype "bidirectional"))
      (node (ref "U$1") (pin "3") (pinfunction "3_3") (pintype "bidirectional"))
    )
    (net (code "69") (name "Net-(DISP1-VO)") (class "Default")
      (node (ref "DISP1") (pin "3") (pinfunction "VO_3") (pintype "bidirectional"))
      (node (ref "U$1") (pin "2") (pinfunction "2_2") (pintype "bidirectional"))
    )
    (net (code "70") (name "Net-(DRV-PadC)") (class "Default")
      (node (ref "DRV") (pin "C") (pinfunction "C_C") (pintype "passive"))
      (node (ref "R42") (pin "2") (pinfunction "2_2") (pintype "passive"))
    )
    (net (code "71") (name "Net-(IC3-ADJ)") (class "Default")
      (node (ref "IC3") (pin "1") (pinfunction "ADJ_1") (pintype "input"))
      (node (ref "R19") (pin "1") (pinfunction "1_1") (pintype "passive"))
      (node (ref "VDET") (pin "1") (pinfunction "1_1") (pintype "bidirectional"))
    )
    (net (code "72") (name "Net-(IC4G-PD0{slash}OSC<=)") (class "Default")
      (node (ref "C2") (pin "1") (pinfunction "1_1") (pintype "passive"))
      (node (ref "IC4") (pin "5") (pinfunction "PD0/OSC<=_5") (pintype "bidirectional"))
      (node (ref "Y1") (pin "2") (pinfunction "OUT/IN_2") (pintype "passive"))
    )
    (net (code "73") (name "Net-(IC4G-PD1{slash}OSC=>)") (class "Default")
      (node (ref "C3") (pin "1") (pinfunction "1_1") (pintype "passive"))
      (node (ref "IC4") (pin "6") (pinfunction "PD1/OSC=>_6") (pintype "bidirectional"))
      (node (ref "Y1") (pin "1") (pinfunction "IN/OUT_1") (pintype "passive"))
    )
    (net (code "74") (name "Net-(IC5-Pad3)") (class "Default")
      (node (ref "IC5") (pin "3") (pinfunction "3_3") (pintype "passive"))
      (node (ref "R9") (pin "1") (pinfunction "1_1") (pintype "passive"))
    )
    (net (code "75") (name "Net-(IC5-Pad5)") (class "Default")
      (node (ref "IC5") (pin "5") (pinfunction "5_5") (pintype "passive"))
      (node (ref "R10") (pin "2") (pinfunction "2_2") (pintype "passive"))
    )
    (net (code "76") (name "Net-(IC6-Pad3)") (class "Default")
      (node (ref "IC6") (pin "3") (pinfunction "3_3") (pintype "passive"))
      (node (ref "R6") (pin "2") (pinfunction "2_2") (pintype "passive"))
    )
    (net (code "77") (name "Net-(IC6-Pad5)") (class "Default")
      (node (ref "IC6") (pin "5") (pinfunction "5_5") (pintype "passive"))
      (node (ref "R3") (pin "1") (pinfunction "1_1") (pintype "passive"))
    )
    (net (code "78") (name "Net-(L1-P$2)") (class "Default")
      (node (ref "C10") (pin "1") (pinfunction "1_1") (pintype "passive"))
      (node (ref "L1") (pin "2") (pinfunction "P$2_2") (pintype "bidirectional"))
      (node (ref "U1") (pin "5") (pinfunction "SW_5") (pintype "power_in"))
    )
    (net (code "79") (name "Net-(LOGIC-PadC)") (class "Default")
      (node (ref "LOGIC") (pin "C") (pinfunction "C_C") (pintype "passive"))
      (node (ref "R40") (pin "2") (pinfunction "2_2") (pintype "passive"))
    )
    (net (code "80") (name "Net-(PWR-PadC)") (class "Default")
      (node (ref "PWR") (pin "C") (pinfunction "C_C") (pintype "passive"))
      (node (ref "R39") (pin "2") (pinfunction "2_2") (pintype "passive"))
    )
    (net (code "81") (name "Net-(Q1-B)") (class "Default")
      (node (ref "Q1") (pin "2") (pinfunction "B_2") (pintype "passive"))
      (node (ref "R3") (pin "2") (pinfunction "2_2") (pintype "passive"))
      (node (ref "R4") (pin "2") (pinfunction "2_2") (pintype "passive"))
    )
    (net (code "82") (name "Net-(Q1-E)") (class "Default")
      (node (ref "Q1") (pin "3") (pinfunction "E_3") (pintype "passive"))
      (node (ref "R5") (pin "2") (pinfunction "2_2") (pintype "passive"))
    )
    (net (code "83") (name "Net-(Q2-B)") (class "Default")
      (node (ref "Q2") (pin "2") (pinfunction "B_2") (pintype "passive"))
      (node (ref "R6") (pin "1") (pinfunction "1_1") (pintype "passive"))
      (node (ref "R7") (pin "2") (pinfunction "2_2") (pintype "passive"))
    )
    (net (code "84") (name "Net-(Q2-E)") (class "Default")
      (node (ref "Q2") (pin "3") (pinfunction "E_3") (pintype "passive"))
      (node (ref "R8") (pin "2") (pinfunction "2_2") (pintype "passive"))
    )
    (net (code "85") (name "Net-(Q3-B)") (class "Default")
      (node (ref "Q3") (pin "2") (pinfunction "B_2") (pintype "passive"))
      (node (ref "R11") (pin "2") (pinfunction "2_2") (pintype "passive"))
      (node (ref "R9") (pin "2") (pinfunction "2_2") (pintype "passive"))
    )
    (net (code "86") (name "Net-(Q3-E)") (class "Default")
      (node (ref "Q3") (pin "3") (pinfunction "E_3") (pintype "passive"))
      (node (ref "R12") (pin "2") (pinfunction "2_2") (pintype "passive"))
    )
    (net (code "87") (name "Net-(Q4-B)") (class "Default")
      (node (ref "Q4") (pin "2") (pinfunction "B_2") (pintype "passive"))
      (node (ref "R10") (pin "1") (pinfunction "1_1") (pintype "passive"))
      (node (ref "R14") (pin "2") (pinfunction "2_2") (pintype "passive"))
    )
    (net (code "88") (name "Net-(Q4-E)") (class "Default")
      (node (ref "Q4") (pin "3") (pinfunction "E_3") (pintype "passive"))
      (node (ref "R13") (pin "2") (pinfunction "2_2") (pintype "passive"))
    )
    (net (code "89") (name "Net-(SW_DET-NC)") (class "Default")
      (node (ref "R35") (pin "2") (pinfunction "2_2") (pintype "passive"))
      (node (ref "SW_DET") (pin "1") (pinfunction "NC_1") (pintype "bidirectional"))
    )
    (net (code "90") (name "Net-(SW_DRV-NC)") (class "Default")
      (node (ref "R37") (pin "2") (pinfunction "2_2") (pintype "passive"))
      (node (ref "SW_DRV") (pin "1") (pinfunction "NC_1") (pintype "bidirectional"))
    )
    (net (code "91") (name "Net-(SW_LOGIC-NC)") (class "Default")
      (node (ref "R38") (pin "2") (pinfunction "2_2") (pintype "passive"))
      (node (ref "SW_LOGIC") (pin "1") (pinfunction "NC_1") (pintype "bidirectional"))
    )
    (net (code "92") (name "Net-(U1-BST)") (class "Default")
      (node (ref "C10") (pin "2") (pinfunction "2_2") (pintype "passive"))
      (node (ref "U1") (pin "6") (pinfunction "BST_6") (pintype "input"))
    )
    (net (code "93") (name "unconnected-(MUSIC_OUT-Pad3)") (class "Default")
      (node (ref "MUSIC_OUT") (pin "3") (pinfunction "3_3") (pintype "bidirectional"))
    )
    (net (code "94") (name "unconnected-(TRIM+-Pad3)") (class "Default")
      (node (ref "TRIM+") (pin "3") (pinfunction "3_3") (pintype "bidirectional"))
    )
    (net (code "95") (name "unconnected-(TRIM--Pad3)") (class "Default")
      (node (ref "TRIM-") (pin "3") (pinfunction "3_3") (pintype "bidirectional"))
    )
    (net (code "96") (name "unconnected-(VDET-Pad3)") (class "Default")
      (node (ref "VDET") (pin "3") (pinfunction "3_3") (pintype "bidirectional"))
    )
  )
)
